# S7CAS-PLEIADES-CARTE-MERE_Pxx_PHY.net
KiCad netlist of a schematic drawn in Altium Designer
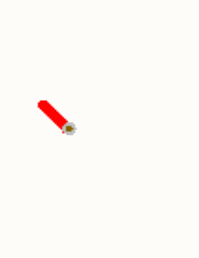
[diagram p0: S7CAS-PLEIADES-CARTE-MERE_Pxx_PHY.SchDoc, left]
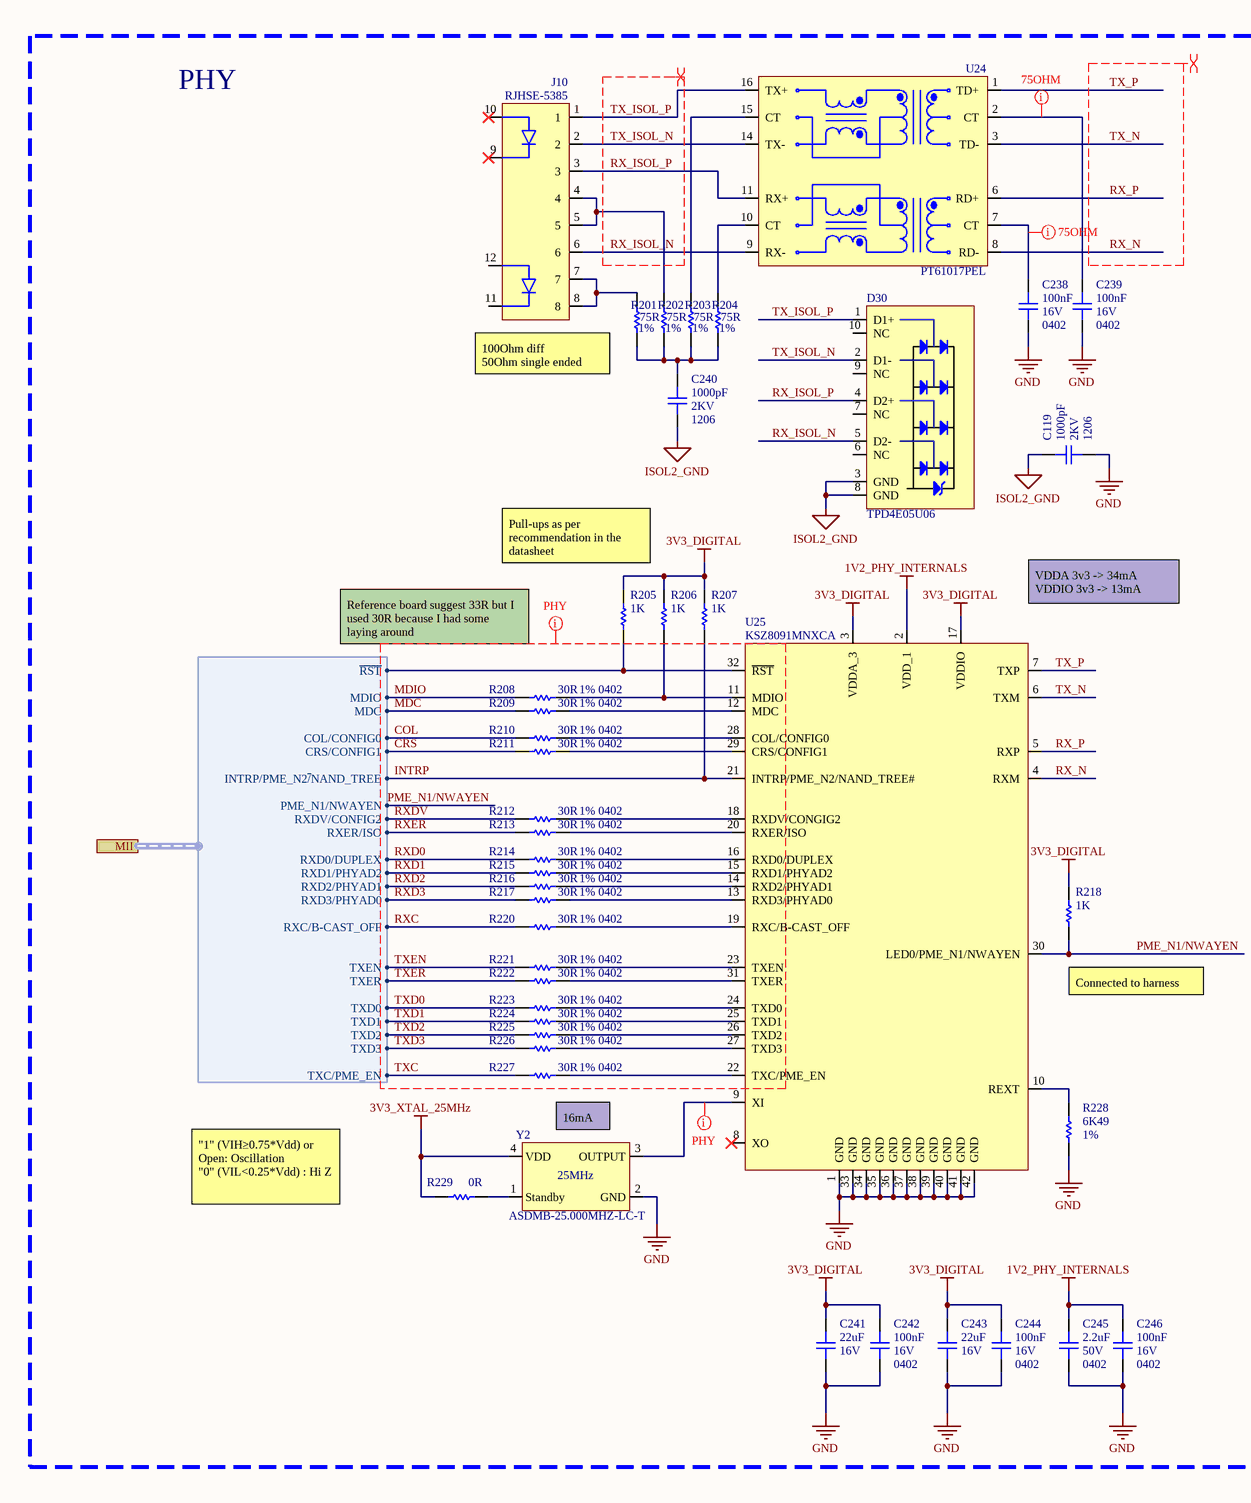
[diagram p1: S7CAS-PLEIADES-CARTE-MERE_Pxx_PHY.SchDoc, middle]
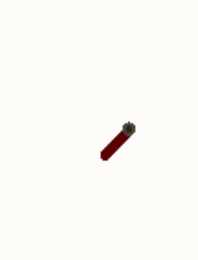
[diagram p2: S7CAS-PLEIADES-CARTE-MERE_Pxx_PHY.SchDoc, right]

(export (version "E")
  (design (tool "Eeschema 10.0.6"))
  (components
    (comp (ref "C119")
      (value "1000pF")
      (footprint "S7CAS_LIB2023:CAP_1206")
      (description "CAP - 1206")
      (fields
        (field (name "VOLTAGE") "2KV")
        (field (name "PACKAGE") "1206")
        (field (name "CREATEDBY") "Jonathan Bouchard")
      )
      (libsource (lib "S7CAS_LIB2023") (part "CAP - 1206"))
    )
    (comp (ref "C238")
      (value "100nF")
      (footprint "S7CAS_LIB2023:CAP_0402")
      (description "CAP - 0402")
      (fields
        (field (name "VOLTAGE") "16V")
        (field (name "PACKAGE") "0402")
        (field (name "Comment") "0402")
        (field (name "CREATEDBY") "Jonathan Bouchard")
      )
      (libsource (lib "S7CAS_LIB2023") (part "CAP - 0603"))
    )
    (comp (ref "C239")
      (value "100nF")
      (footprint "S7CAS_LIB2023:CAP_0402")
      (description "CAP - 0402")
      (fields
        (field (name "VOLTAGE") "16V")
        (field (name "PACKAGE") "0402")
        (field (name "Comment") "0402")
        (field (name "CREATEDBY") "Jonathan Bouchard")
      )
      (libsource (lib "S7CAS_LIB2023") (part "CAP - 0603"))
    )
    (comp (ref "C240")
      (value "1000pF")
      (footprint "S7CAS_LIB2023:CAP_1206")
      (description "CAP - 1206")
      (fields
        (field (name "VOLTAGE") "2KV")
        (field (name "PACKAGE") "1206")
        (field (name "CREATEDBY") "Jonathan Bouchard")
      )
      (libsource (lib "S7CAS_LIB2023") (part "CAP - 1206"))
    )
    (comp (ref "C241")
      (value "22uF")
      (footprint "S7CAS_LIB2023:CAP_1206")
      (description "CAP - 1206")
      (fields (field (name "VOLTAGE") "16V") (field (name "CREATEDBY") "Jonathan Bouchard"))
      (libsource (lib "S7CAS_LIB2023") (part "CAP - 1206"))
    )
    (comp (ref "C242")
      (value "100nF")
      (footprint "S7CAS_LIB2023:CAP_0402")
      (description "CAP - 0402")
      (fields
        (field (name "VOLTAGE") "16V")
        (field (name "PACKAGE") "0402")
        (field (name "Comment") "0402")
        (field (name "CREATEDBY") "Jonathan Bouchard")
      )
      (libsource (lib "S7CAS_LIB2023") (part "CAP - 0603"))
    )
    (comp (ref "C243")
      (value "22uF")
      (footprint "S7CAS_LIB2023:CAP_1206")
      (description "CAP - 1206")
      (fields (field (name "VOLTAGE") "16V") (field (name "CREATEDBY") "Jonathan Bouchard"))
      (libsource (lib "S7CAS_LIB2023") (part "CAP - 1206"))
    )
    (comp (ref "C244")
      (value "100nF")
      (footprint "S7CAS_LIB2023:CAP_0402")
      (description "CAP - 0402")
      (fields
        (field (name "VOLTAGE") "16V")
        (field (name "PACKAGE") "0402")
        (field (name "Comment") "0402")
        (field (name "CREATEDBY") "Jonathan Bouchard")
      )
      (libsource (lib "S7CAS_LIB2023") (part "CAP - 0603"))
    )
    (comp (ref "C245")
      (value "2.2uF")
      (footprint "S7CAS_LIB2023:CAP_0402")
      (description "CAP - 0402")
      (fields
        (field (name "VOLTAGE") "50V")
        (field (name "PACKAGE") "0402")
        (field (name "Comment") "0402")
        (field (name "CREATEDBY") "Jonathan Bouchard")
      )
      (libsource (lib "S7CAS_LIB2023") (part "CAP - 0603"))
    )
    (comp (ref "C246")
      (value "100nF")
      (footprint "S7CAS_LIB2023:CAP_0402")
      (description "CAP - 0402")
      (fields
        (field (name "VOLTAGE") "16V")
        (field (name "PACKAGE") "0402")
        (field (name "Comment") "0402")
        (field (name "CREATEDBY") "Jonathan Bouchard")
      )
      (libsource (lib "S7CAS_LIB2023") (part "CAP - 0603"))
    )
    (comp (ref "D30")
      (value "TPD4E05U06")
      (footprint "TVS_DATA_TPD4E05U06")
      (description "TVS - TVS DIODE 5.5VWM 14VC - 10SON")
      (fields
        (field (name "CREATEDBY/DATE") "Olivier Bernard / 12/3/2018")
        (field (name "VERIFIEDBY") "Caroline Paulin / 4 juillet 2018")
      )
      (libsource (lib "S7CAS_LIB2023") (part "TVS_DATA_TPD4E05U06"))
    )
    (comp (ref "J10")
      (value "RJHSE-5385")
      (footprint "CONN_ETHERNET_RJHSE-5385")
      (description "CONN - MOD JACK RJ45 R/A ETHERNET - TH")
      (fields (field (name "MFG") "Amphenol") (field (name "CREATEDBY") "Jonathan Bouchard"))
      (libsource (lib "S7CAS_LIB2023") (part "CONN_ETHERNET_RJHSE-5385"))
    )
    (comp (ref "R201")
      (value "75R")
      (footprint "S7CAS_LIB2023:RES_0402")
      (description "RES - 0402")
      (fields
        (field (name "PRECISION") "1%")
        (field (name "Comment") "RES - 0603")
        (field (name "CREATEDBY") "Jonathan Bouchard")
      )
      (libsource (lib "S7CAS_LIB2023") (part "RES - 0603"))
    )
    (comp (ref "R202")
      (value "75R")
      (footprint "S7CAS_LIB2023:RES_0402")
      (description "RES - 0402")
      (fields
        (field (name "PRECISION") "1%")
        (field (name "Comment") "RES - 0603")
        (field (name "CREATEDBY") "Jonathan Bouchard")
      )
      (libsource (lib "S7CAS_LIB2023") (part "RES - 0603"))
    )
    (comp (ref "R203")
      (value "75R")
      (footprint "S7CAS_LIB2023:RES_0402")
      (description "RES - 0402")
      (fields
        (field (name "PRECISION") "1%")
        (field (name "Comment") "RES - 0603")
        (field (name "CREATEDBY") "Jonathan Bouchard")
      )
      (libsource (lib "S7CAS_LIB2023") (part "RES - 0603"))
    )
    (comp (ref "R204")
      (value "75R")
      (footprint "S7CAS_LIB2023:RES_0402")
      (description "RES - 0402")
      (fields
        (field (name "PRECISION") "1%")
        (field (name "Comment") "RES - 0603")
        (field (name "CREATEDBY") "Jonathan Bouchard")
      )
      (libsource (lib "S7CAS_LIB2023") (part "RES - 0603"))
    )
    (comp (ref "R205")
      (value "1K")
      (footprint "S7CAS_LIB2023:RES_0402")
      (description "RES - 0402")
      (fields (field (name "Comment") "RES - 0603") (field (name "CREATEDBY") "Jonathan Bouchard"))
      (libsource (lib "S7CAS_LIB2023") (part "RES - 0603"))
    )
    (comp (ref "R206")
      (value "1K")
      (footprint "S7CAS_LIB2023:RES_0402")
      (description "RES - 0402")
      (fields (field (name "Comment") "RES - 0603") (field (name "CREATEDBY") "Jonathan Bouchard"))
      (libsource (lib "S7CAS_LIB2023") (part "RES - 0603"))
    )
    (comp (ref "R207")
      (value "1K")
      (footprint "S7CAS_LIB2023:RES_0402")
      (description "RES - 0402")
      (fields (field (name "Comment") "RES - 0603") (field (name "CREATEDBY") "Jonathan Bouchard"))
      (libsource (lib "S7CAS_LIB2023") (part "RES - 0603"))
    )
    (comp (ref "R208")
      (value "30R")
      (footprint "S7CAS_LIB2023:RES_0402")
      (description "RES - 0402")
      (fields
        (field (name "PACKAGE") "0402")
        (field (name "PRECISION") "1%")
        (field (name "Comment") "RES - 0603")
        (field (name "CREATEDBY") "Jonathan Bouchard")
      )
      (libsource (lib "S7CAS_LIB2023") (part "RES - 0603"))
    )
    (comp (ref "R209")
      (value "30R")
      (footprint "S7CAS_LIB2023:RES_0402")
      (description "RES - 0402")
      (fields
        (field (name "PACKAGE") "0402")
        (field (name "PRECISION") "1%")
        (field (name "Comment") "RES - 0603")
        (field (name "CREATEDBY") "Jonathan Bouchard")
      )
      (libsource (lib "S7CAS_LIB2023") (part "RES - 0603"))
    )
    (comp (ref "R210")
      (value "30R")
      (footprint "S7CAS_LIB2023:RES_0402")
      (description "RES - 0402")
      (fields
        (field (name "PACKAGE") "0402")
        (field (name "PRECISION") "1%")
        (field (name "Comment") "RES - 0603")
        (field (name "CREATEDBY") "Jonathan Bouchard")
      )
      (libsource (lib "S7CAS_LIB2023") (part "RES - 0603"))
    )
    (comp (ref "R211")
      (value "30R")
      (footprint "S7CAS_LIB2023:RES_0402")
      (description "RES - 0402")
      (fields
        (field (name "PACKAGE") "0402")
        (field (name "PRECISION") "1%")
        (field (name "Comment") "RES - 0603")
        (field (name "CREATEDBY") "Jonathan Bouchard")
      )
      (libsource (lib "S7CAS_LIB2023") (part "RES - 0603"))
    )
    (comp (ref "R212")
      (value "30R")
      (footprint "S7CAS_LIB2023:RES_0402")
      (description "RES - 0402")
      (fields
        (field (name "PACKAGE") "0402")
        (field (name "PRECISION") "1%")
        (field (name "Comment") "RES - 0603")
        (field (name "CREATEDBY") "Jonathan Bouchard")
      )
      (libsource (lib "S7CAS_LIB2023") (part "RES - 0603"))
    )
    (comp (ref "R213")
      (value "30R")
      (footprint "S7CAS_LIB2023:RES_0402")
      (description "RES - 0402")
      (fields
        (field (name "PACKAGE") "0402")
        (field (name "PRECISION") "1%")
        (field (name "Comment") "RES - 0603")
        (field (name "CREATEDBY") "Jonathan Bouchard")
      )
      (libsource (lib "S7CAS_LIB2023") (part "RES - 0603"))
    )
    (comp (ref "R214")
      (value "30R")
      (footprint "S7CAS_LIB2023:RES_0402")
      (description "RES - 0402")
      (fields
        (field (name "PACKAGE") "0402")
        (field (name "PRECISION") "1%")
        (field (name "Comment") "RES - 0603")
        (field (name "CREATEDBY") "Jonathan Bouchard")
      )
      (libsource (lib "S7CAS_LIB2023") (part "RES - 0603"))
    )
    (comp (ref "R215")
      (value "30R")
      (footprint "S7CAS_LIB2023:RES_0402")
      (description "RES - 0402")
      (fields
        (field (name "PACKAGE") "0402")
        (field (name "PRECISION") "1%")
        (field (name "Comment") "RES - 0603")
        (field (name "CREATEDBY") "Jonathan Bouchard")
      )
      (libsource (lib "S7CAS_LIB2023") (part "RES - 0603"))
    )
    (comp (ref "R216")
      (value "30R")
      (footprint "S7CAS_LIB2023:RES_0402")
      (description "RES - 0402")
      (fields
        (field (name "PACKAGE") "0402")
        (field (name "PRECISION") "1%")
        (field (name "Comment") "RES - 0603")
        (field (name "CREATEDBY") "Jonathan Bouchard")
      )
      (libsource (lib "S7CAS_LIB2023") (part "RES - 0603"))
    )
    (comp (ref "R217")
      (value "30R")
      (footprint "S7CAS_LIB2023:RES_0402")
      (description "RES - 0402")
      (fields
        (field (name "PACKAGE") "0402")
        (field (name "PRECISION") "1%")
        (field (name "Comment") "RES - 0603")
        (field (name "CREATEDBY") "Jonathan Bouchard")
      )
      (libsource (lib "S7CAS_LIB2023") (part "RES - 0603"))
    )
    (comp (ref "R218")
      (value "1K")
      (footprint "S7CAS_LIB2023:RES_0402")
      (description "RES - 0402")
      (fields (field (name "Comment") "RES - 0603") (field (name "CREATEDBY") "Jonathan Bouchard"))
      (libsource (lib "S7CAS_LIB2023") (part "RES - 0603"))
    )
    (comp (ref "R220")
      (value "30R")
      (footprint "S7CAS_LIB2023:RES_0402")
      (description "RES - 0402")
      (fields
        (field (name "PACKAGE") "0402")
        (field (name "PRECISION") "1%")
        (field (name "Comment") "RES - 0603")
        (field (name "CREATEDBY") "Jonathan Bouchard")
      )
      (libsource (lib "S7CAS_LIB2023") (part "RES - 0603"))
    )
    (comp (ref "R221")
      (value "30R")
      (footprint "S7CAS_LIB2023:RES_0402")
      (description "RES - 0402")
      (fields
        (field (name "PACKAGE") "0402")
        (field (name "PRECISION") "1%")
        (field (name "Comment") "RES - 0603")
        (field (name "CREATEDBY") "Jonathan Bouchard")
      )
      (libsource (lib "S7CAS_LIB2023") (part "RES - 0603"))
    )
    (comp (ref "R222")
      (value "30R")
      (footprint "S7CAS_LIB2023:RES_0402")
      (description "RES - 0402")
      (fields
        (field (name "PACKAGE") "0402")
        (field (name "PRECISION") "1%")
        (field (name "Comment") "RES - 0603")
        (field (name "CREATEDBY") "Jonathan Bouchard")
      )
      (libsource (lib "S7CAS_LIB2023") (part "RES - 0603"))
    )
    (comp (ref "R223")
      (value "30R")
      (footprint "S7CAS_LIB2023:RES_0402")
      (description "RES - 0402")
      (fields
        (field (name "PACKAGE") "0402")
        (field (name "PRECISION") "1%")
        (field (name "Comment") "RES - 0603")
        (field (name "CREATEDBY") "Jonathan Bouchard")
      )
      (libsource (lib "S7CAS_LIB2023") (part "RES - 0603"))
    )
    (comp (ref "R224")
      (value "30R")
      (footprint "S7CAS_LIB2023:RES_0402")
      (description "RES - 0402")
      (fields
        (field (name "PACKAGE") "0402")
        (field (name "PRECISION") "1%")
        (field (name "Comment") "RES - 0603")
        (field (name "CREATEDBY") "Jonathan Bouchard")
      )
      (libsource (lib "S7CAS_LIB2023") (part "RES - 0603"))
    )
    (comp (ref "R225")
      (value "30R")
      (footprint "S7CAS_LIB2023:RES_0402")
      (description "RES - 0402")
      (fields
        (field (name "PACKAGE") "0402")
        (field (name "PRECISION") "1%")
        (field (name "Comment") "RES - 0603")
        (field (name "CREATEDBY") "Jonathan Bouchard")
      )
      (libsource (lib "S7CAS_LIB2023") (part "RES - 0603"))
    )
    (comp (ref "R226")
      (value "30R")
      (footprint "S7CAS_LIB2023:RES_0402")
      (description "RES - 0402")
      (fields
        (field (name "PACKAGE") "0402")
        (field (name "PRECISION") "1%")
        (field (name "Comment") "RES - 0603")
        (field (name "CREATEDBY") "Jonathan Bouchard")
      )
      (libsource (lib "S7CAS_LIB2023") (part "RES - 0603"))
    )
    (comp (ref "R227")
      (value "30R")
      (footprint "S7CAS_LIB2023:RES_0402")
      (description "RES - 0402")
      (fields
        (field (name "PACKAGE") "0402")
        (field (name "PRECISION") "1%")
        (field (name "Comment") "RES - 0603")
        (field (name "CREATEDBY") "Jonathan Bouchard")
      )
      (libsource (lib "S7CAS_LIB2023") (part "RES - 0603"))
    )
    (comp (ref "R228")
      (value "6K49")
      (footprint "RES_0402")
      (description "RES - 0402")
      (fields
        (field (name "VOLTAGE") "50V")
        (field (name "POWER") "1/16W")
        (field (name "PRECISION") "1%")
        (field (name "CREATEDBY") "Jonathan Bouchard")
      )
      (libsource (lib "S7CAS_LIB2023") (part "RES - 0402"))
    )
    (comp (ref "R229")
      (value "0R")
      (footprint "S7CAS_LIB2023:RES_0402")
      (description "RES - 0402")
      (fields (field (name "Comment") "RES - 0603") (field (name "CREATEDBY") "Jonathan Bouchard"))
      (libsource (lib "S7CAS_LIB2023") (part "RES - 0603"))
    )
    (comp (ref "U24")
      (value "PT61017PEL")
      (footprint "ISO_PT61017PEL")
      (description "ISO - 350µH LAN 10/100 Base-T Pulse Transformer 1CT:1CT Surface Mount")
      (libsource (lib "S7CAS_LIB2023") (part "ISO_PT61017PEL"))
    )
    (comp (ref "U25")
      (value "KSZ8091MNXCA")
      (footprint "COM_ETH_PHY_KSZ8091MNXCA")
      (description "COM - ETHERNET PHY 10/100 - QFN-32")
      (fields
        (field (name "VOLTAGE") "1.8V, 2.5V, 3.3V")
        (field (name "MFG") "Micrel")
        (field (name "CREATEDBY") "Jonathan Bouchard")
      )
      (libsource (lib "S7CAS_LIB2023") (part "COM_ETH_PHY_KSZ8091MNXCA"))
    )
    (comp (ref "Y2")
      (value "ASDMB-25.000MHZ-LC-T")
      (footprint "OSC_ASDMB-25.000MHZ-LC-T")
      (description "OSC - 25MHz XO (Standard) LVCMOS - 4-SMD, No Lead")
      (fields
        (field (name "TOLERANCE") "±50ppm")
        (field (name "CREATEDBY/DATE") "Joël Lemay 2019-03-29")
        (field (name "VERIFIEDBY") "C. Paulin - 29 mai 2019")
      )
      (libsource (lib "S7CAS_LIB2023") (part "OSC_ASDMB-25.000MHZ-LC-T"))
    )
  )
  (nets
    (net (code "4") (name "/COL") (class "Default")
      (node (ref "R210") (pin "1") (pinfunction "1_1") (pintype "passive"))
    )
    (net (code "5") (name "/CRS") (class "Default")
      (node (ref "R211") (pin "1") (pinfunction "1_1") (pintype "passive"))
    )
    (net (code "6") (name "/INTRP") (class "Default")
      (node (ref "R207") (pin "1") (pinfunction "1_1") (pintype "passive"))
      (node (ref "U25") (pin "21") (pinfunction "INTRP/PME_N2/NAND_TREE#_21") (pintype "passive"))
    )
    (net (code "7") (name "/MDC") (class "Default")
      (node (ref "R209") (pin "1") (pinfunction "1_1") (pintype "passive"))
    )
    (net (code "8") (name "/MDIO") (class "Default")
      (node (ref "R208") (pin "1") (pinfunction "1_1") (pintype "passive"))
    )
    (net (code "9") (name "/PME_N1{slash}NWAYEN") (class "Default")
      (node (ref "R218") (pin "1") (pinfunction "1_1") (pintype "passive"))
      (node (ref "U25") (pin "30") (pinfunction "LED0/PME_N1/NWAYEN_30") (pintype "passive"))
    )
    (net (code "10") (name "/RXC") (class "Default")
      (node (ref "R220") (pin "1") (pinfunction "1_1") (pintype "passive"))
    )
    (net (code "11") (name "/RXD0") (class "Default")
      (node (ref "R214") (pin "1") (pinfunction "1_1") (pintype "passive"))
    )
    (net (code "12") (name "/RXD1") (class "Default")
      (node (ref "R215") (pin "1") (pinfunction "1_1") (pintype "passive"))
    )
    (net (code "13") (name "/RXD2") (class "Default")
      (node (ref "R216") (pin "1") (pinfunction "1_1") (pintype "passive"))
    )
    (net (code "14") (name "/RXD3") (class "Default")
      (node (ref "R217") (pin "1") (pinfunction "1_1") (pintype "passive"))
    )
    (net (code "15") (name "/RXDV") (class "Default")
      (node (ref "R212") (pin "1") (pinfunction "1_1") (pintype "passive"))
    )
    (net (code "16") (name "/RXER") (class "Default")
      (node (ref "R213") (pin "1") (pinfunction "1_1") (pintype "passive"))
    )
    (net (code "17") (name "/RX_ISOL_N") (class "Default")
      (node (ref "D30") (pin "5") (pinfunction "D2-_5") (pintype "passive"))
      (node (ref "J10") (pin "6") (pinfunction "6_6") (pintype "passive"))
      (node (ref "U24") (pin "9") (pinfunction "RX-_9") (pintype "passive"))
    )
    (net (code "18") (name "/RX_ISOL_P") (class "Default")
      (node (ref "D30") (pin "4") (pinfunction "D2+_4") (pintype "passive"))
      (node (ref "J10") (pin "3") (pinfunction "3_3") (pintype "passive"))
      (node (ref "U24") (pin "11") (pinfunction "RX+_11") (pintype "passive"))
    )
    (net (code "19") (name "/RX_N") (class "Default")
      (node (ref "U24") (pin "8") (pinfunction "RD-_8") (pintype "passive"))
      (node (ref "U25") (pin "4") (pinfunction "RXM_4") (pintype "passive"))
    )
    (net (code "20") (name "/RX_P") (class "Default")
      (node (ref "U24") (pin "6") (pinfunction "RD+_6") (pintype "passive"))
      (node (ref "U25") (pin "5") (pinfunction "RXP_5") (pintype "passive"))
    )
    (net (code "21") (name "/TXC") (class "Default")
      (node (ref "R227") (pin "1") (pinfunction "1_1") (pintype "passive"))
    )
    (net (code "22") (name "/TXD0") (class "Default")
      (node (ref "R223") (pin "1") (pinfunction "1_1") (pintype "passive"))
    )
    (net (code "23") (name "/TXD1") (class "Default")
      (node (ref "R224") (pin "1") (pinfunction "1_1") (pintype "passive"))
    )
    (net (code "24") (name "/TXD2") (class "Default")
      (node (ref "R225") (pin "1") (pinfunction "1_1") (pintype "passive"))
    )
    (net (code "25") (name "/TXD3") (class "Default")
      (node (ref "R226") (pin "1") (pinfunction "1_1") (pintype "passive"))
    )
    (net (code "26") (name "/TXEN") (class "Default")
      (node (ref "R221") (pin "1") (pinfunction "1_1") (pintype "passive"))
    )
    (net (code "27") (name "/TXER") (class "Default")
      (node (ref "R222") (pin "1") (pinfunction "1_1") (pintype "passive"))
    )
    (net (code "28") (name "/TX_ISOL_N") (class "Default")
      (node (ref "D30") (pin "2") (pinfunction "D1-_2") (pintype "passive"))
      (node (ref "J10") (pin "2") (pinfunction "2_2") (pintype "passive"))
      (node (ref "U24") (pin "14") (pinfunction "TX-_14") (pintype "passive"))
    )
    (net (code "29") (name "/TX_ISOL_P") (class "Default")
      (node (ref "D30") (pin "1") (pinfunction "D1+_1") (pintype "passive"))
      (node (ref "J10") (pin "1") (pinfunction "1_1") (pintype "passive"))
      (node (ref "U24") (pin "16") (pinfunction "TX+_16") (pintype "passive"))
    )
    (net (code "30") (name "/TX_N") (class "Default")
      (node (ref "U24") (pin "3") (pinfunction "TD-_3") (pintype "passive"))
      (node (ref "U25") (pin "6") (pinfunction "TXM_6") (pintype "passive"))
    )
    (net (code "31") (name "/TX_P") (class "Default")
      (node (ref "U24") (pin "1") (pinfunction "TD+_1") (pintype "passive"))
      (node (ref "U25") (pin "7") (pinfunction "TXP_7") (pintype "passive"))
    )
    (net (code "33") (name "1V2_PHY_INTERNALS") (class "Default")
      (node (ref "C245") (pin "2") (pinfunction "2_2") (pintype "passive"))
      (node (ref "C246") (pin "2") (pinfunction "2_2") (pintype "passive"))
      (node (ref "U25") (pin "2") (pinfunction "VDD_1_2") (pintype "power_in"))
    )
    (net (code "34") (name "3V3_DIGITAL") (class "Default")
      (node (ref "C241") (pin "2") (pinfunction "2_2") (pintype "passive"))
      (node (ref "C242") (pin "2") (pinfunction "2_2") (pintype "passive"))
      (node (ref "C243") (pin "2") (pinfunction "2_2") (pintype "passive"))
      (node (ref "C244") (pin "2") (pinfunction "2_2") (pintype "passive"))
      (node (ref "R205") (pin "2") (pinfunction "2_2") (pintype "passive"))
      (node (ref "R206") (pin "2") (pinfunction "2_2") (pintype "passive"))
      (node (ref "R207") (pin "2") (pinfunction "2_2") (pintype "passive"))
      (node (ref "R218") (pin "2") (pinfunction "2_2") (pintype "passive"))
      (node (ref "U25") (pin "17") (pinfunction "VDDIO_17") (pintype "power_in"))
      (node (ref "U25") (pin "3") (pinfunction "VDDA_3_3") (pintype "power_in"))
    )
    (net (code "35") (name "3V3_XTAL_25MHz") (class "Default")
      (node (ref "R229") (pin "2") (pinfunction "2_2") (pintype "passive"))
      (node (ref "Y2") (pin "4") (pinfunction "VDD_4") (pintype "passive"))
    )
    (net (code "36") (name "GND") (class "Default")
      (node (ref "C119") (pin "1") (pinfunction "1_1") (pintype "passive"))
      (node (ref "C238") (pin "1") (pinfunction "1_1") (pintype "passive"))
      (node (ref "C239") (pin "1") (pinfunction "1_1") (pintype "passive"))
      (node (ref "C241") (pin "1") (pinfunction "1_1") (pintype "passive"))
      (node (ref "C242") (pin "1") (pinfunction "1_1") (pintype "passive"))
      (node (ref "C243") (pin "1") (pinfunction "1_1") (pintype "passive"))
      (node (ref "C244") (pin "1") (pinfunction "1_1") (pintype "passive"))
      (node (ref "C245") (pin "1") (pinfunction "1_1") (pintype "passive"))
      (node (ref "C246") (pin "1") (pinfunction "1_1") (pintype "passive"))
      (node (ref "R228") (pin "1") (pinfunction "1_1") (pintype "passive"))
      (node (ref "U25") (pin "1") (pinfunction "GND_1") (pintype "passive"))
      (node (ref "U25") (pin "33") (pinfunction "GND_33") (pintype "passive"))
      (node (ref "U25") (pin "34") (pinfunction "GND_34") (pintype "passive"))
      (node (ref "U25") (pin "35") (pinfunction "GND_35") (pintype "passive"))
      (node (ref "U25") (pin "36") (pinfunction "GND_36") (pintype "passive"))
      (node (ref "U25") (pin "37") (pinfunction "GND_37") (pintype "passive"))
      (node (ref "U25") (pin "38") (pinfunction "GND_38") (pintype "passive"))
      (node (ref "U25") (pin "39") (pinfunction "GND_39") (pintype "passive"))
      (node (ref "U25") (pin "40") (pinfunction "GND_40") (pintype "passive"))
      (node (ref "U25") (pin "41") (pinfunction "GND_41") (pintype "passive"))
      (node (ref "U25") (pin "42") (pinfunction "GND_42") (pintype "passive"))
      (node (ref "Y2") (pin "2") (pinfunction "GND_2") (pintype "passive"))
    )
    (net (code "37") (name "ISOL2_GND") (class "Default")
      (node (ref "C119") (pin "2") (pinfunction "2_2") (pintype "passive"))
      (node (ref "C240") (pin "1") (pinfunction "1_1") (pintype "passive"))
      (node (ref "D30") (pin "3") (pinfunction "GND_3") (pintype "passive"))
      (node (ref "D30") (pin "8") (pinfunction "GND_8") (pintype "passive"))
    )
    (net (code "38") (name "Net-(C238-Pad2)") (class "Default")
      (node (ref "C238") (pin "2") (pinfunction "2_2") (pintype "passive"))
      (node (ref "U24") (pin "7") (pinfunction "CT_7") (pintype "passive"))
    )
    (net (code "39") (name "Net-(C239-Pad2)") (class "Default")
      (node (ref "C239") (pin "2") (pinfunction "2_2") (pintype "passive"))
      (node (ref "U24") (pin "2") (pinfunction "CT_2") (pintype "passive"))
    )
    (net (code "40") (name "Net-(C240-Pad2)") (class "Default")
      (node (ref "C240") (pin "2") (pinfunction "2_2") (pintype "passive"))
      (node (ref "R201") (pin "1") (pinfunction "1_1") (pintype "passive"))
      (node (ref "R202") (pin "1") (pinfunction "1_1") (pintype "passive"))
      (node (ref "R203") (pin "1") (pinfunction "1_1") (pintype "passive"))
      (node (ref "R204") (pin "1") (pinfunction "1_1") (pintype "passive"))
    )
    (net (code "41") (name "Net-(J10-Pad4)") (class "Default")
      (node (ref "J10") (pin "4") (pinfunction "4_4") (pintype "passive"))
      (node (ref "J10") (pin "5") (pinfunction "5_5") (pintype "passive"))
      (node (ref "R202") (pin "2") (pinfunction "2_2") (pintype "passive"))
    )
    (net (code "42") (name "Net-(J10-Pad7)") (class "Default")
      (node (ref "J10") (pin "7") (pinfunction "7_7") (pintype "passive"))
      (node (ref "J10") (pin "8") (pinfunction "8_8") (pintype "passive"))
      (node (ref "R201") (pin "2") (pinfunction "2_2") (pintype "passive"))
    )
    (net (code "43") (name "Net-(R203-Pad2)") (class "Default")
      (node (ref "R203") (pin "2") (pinfunction "2_2") (pintype "passive"))
      (node (ref "U24") (pin "15") (pinfunction "CT_15") (pintype "passive"))
    )
    (net (code "44") (name "Net-(R204-Pad2)") (class "Default")
      (node (ref "R204") (pin "2") (pinfunction "2_2") (pintype "passive"))
      (node (ref "U24") (pin "10") (pinfunction "CT_10") (pintype "passive"))
    )
    (net (code "45") (name "Net-(U25-COL{slash}CONFIG0)") (class "Default")
      (node (ref "R210") (pin "2") (pinfunction "2_2") (pintype "passive"))
      (node (ref "U25") (pin "28") (pinfunction "COL/CONFIG0_28") (pintype "passive"))
    )
    (net (code "46") (name "Net-(U25-CRS{slash}CONFIG1)") (class "Default")
      (node (ref "R211") (pin "2") (pinfunction "2_2") (pintype "passive"))
      (node (ref "U25") (pin "29") (pinfunction "CRS/CONFIG1_29") (pintype "passive"))
    )
    (net (code "47") (name "Net-(U25-MDC)") (class "Default")
      (node (ref "R209") (pin "2") (pinfunction "2_2") (pintype "passive"))
      (node (ref "U25") (pin "12") (pinfunction "MDC_12") (pintype "passive"))
    )
    (net (code "48") (name "Net-(U25-MDIO)") (class "Default")
      (node (ref "R206") (pin "1") (pinfunction "1_1") (pintype "passive"))
      (node (ref "R208") (pin "2") (pinfunction "2_2") (pintype "passive"))
      (node (ref "U25") (pin "11") (pinfunction "MDIO_11") (pintype "passive"))
    )
    (net (code "49") (name "Net-(U25-REXT)") (class "Default")
      (node (ref "R228") (pin "2") (pinfunction "2_2") (pintype "passive"))
      (node (ref "U25") (pin "10") (pinfunction "REXT_10") (pintype "passive"))
    )
    (net (code "50") (name "Net-(U25-RST)") (class "Default")
      (node (ref "R205") (pin "1") (pinfunction "1_1") (pintype "passive"))
      (node (ref "U25") (pin "32") (pinfunction "RST_32") (pintype "passive"))
    )
    (net (code "51") (name "Net-(U25-RXC{slash}B-CAST_OFF)") (class "Default")
      (node (ref "R220") (pin "2") (pinfunction "2_2") (pintype "passive"))
      (node (ref "U25") (pin "19") (pinfunction "RXC/B-CAST_OFF_19") (pintype "passive"))
    )
    (net (code "52") (name "Net-(U25-RXD0{slash}DUPLEX)") (class "Default")
      (node (ref "R214") (pin "2") (pinfunction "2_2") (pintype "passive"))
      (node (ref "U25") (pin "16") (pinfunction "RXD0/DUPLEX_16") (pintype "passive"))
    )
    (net (code "53") (name "Net-(U25-RXD1{slash}PHYAD2)") (class "Default")
      (node (ref "R215") (pin "2") (pinfunction "2_2") (pintype "passive"))
      (node (ref "U25") (pin "15") (pinfunction "RXD1/PHYAD2_15") (pintype "passive"))
    )
    (net (code "54") (name "Net-(U25-RXD2{slash}PHYAD1)") (class "Default")
      (node (ref "R216") (pin "2") (pinfunction "2_2") (pintype "passive"))
      (node (ref "U25") (pin "14") (pinfunction "RXD2/PHYAD1_14") (pintype "passive"))
    )
    (net (code "55") (name "Net-(U25-RXD3{slash}PHYAD0)") (class "Default")
      (node (ref "R217") (pin "2") (pinfunction "2_2") (pintype "passive"))
      (node (ref "U25") (pin "13") (pinfunction "RXD3/PHYAD0_13") (pintype "passive"))
    )
    (net (code "56") (name "Net-(U25-RXDV{slash}CONGIG2)") (class "Default")
      (node (ref "R212") (pin "2") (pinfunction "2_2") (pintype "passive"))
      (node (ref "U25") (pin "18") (pinfunction "RXDV/CONGIG2_18") (pintype "passive"))
    )
    (net (code "57") (name "Net-(U25-RXER{slash}ISO)") (class "Default")
      (node (ref "R213") (pin "2") (pinfunction "2_2") (pintype "passive"))
      (node (ref "U25") (pin "20") (pinfunction "RXER/ISO_20") (pintype "passive"))
    )
    (net (code "58") (name "Net-(U25-TXC{slash}PME_EN)") (class "Default")
      (node (ref "R227") (pin "2") (pinfunction "2_2") (pintype "passive"))
      (node (ref "U25") (pin "22") (pinfunction "TXC/PME_EN_22") (pintype "passive"))
    )
    (net (code "59") (name "Net-(U25-TXD0)") (class "Default")
      (node (ref "R223") (pin "2") (pinfunction "2_2") (pintype "passive"))
      (node (ref "U25") (pin "24") (pinfunction "TXD0_24") (pintype "passive"))
    )
    (net (code "60") (name "Net-(U25-TXD1)") (class "Default")
      (node (ref "R224") (pin "2") (pinfunction "2_2") (pintype "passive"))
      (node (ref "U25") (pin "25") (pinfunction "TXD1_25") (pintype "passive"))
    )
    (net (code "61") (name "Net-(U25-TXD2)") (class "Default")
      (node (ref "R225") (pin "2") (pinfunction "2_2") (pintype "passive"))
      (node (ref "U25") (pin "26") (pinfunction "TXD2_26") (pintype "passive"))
    )
    (net (code "62") (name "Net-(U25-TXD3)") (class "Default")
      (node (ref "R226") (pin "2") (pinfunction "2_2") (pintype "passive"))
      (node (ref "U25") (pin "27") (pinfunction "TXD3_27") (pintype "passive"))
    )
    (net (code "63") (name "Net-(U25-TXEN)") (class "Default")
      (node (ref "R221") (pin "2") (pinfunction "2_2") (pintype "passive"))
      (node (ref "U25") (pin "23") (pinfunction "TXEN_23") (pintype "passive"))
    )
    (net (code "64") (name "Net-(U25-TXER)") (class "Default")
      (node (ref "R222") (pin "2") (pinfunction "2_2") (pintype "passive"))
      (node (ref "U25") (pin "31") (pinfunction "TXER_31") (pintype "passive"))
    )
    (net (code "65") (name "Net-(U25-XI)") (class "Default")
      (node (ref "U25") (pin "9") (pinfunction "XI_9") (pintype "passive"))
      (node (ref "Y2") (pin "3") (pinfunction "OUTPUT_3") (pintype "passive"))
    )
    (net (code "66") (name "Net-(Y2-Standby)") (class "Default")
      (node (ref "R229") (pin "1") (pinfunction "1_1") (pintype "passive"))
      (node (ref "Y2") (pin "1") (pinfunction "Standby_1") (pintype "passive"))
    )
    (net (code "67") (name "unconnected-(D30-NC-Pad6)") (class "Default")
      (node (ref "D30") (pin "6") (pinfunction "NC_6") (pintype "passive"))
    )
    (net (code "68") (name "unconnected-(D30-NC-Pad7)") (class "Default")
      (node (ref "D30") (pin "7") (pinfunction "NC_7") (pintype "passive"))
    )
    (net (code "69") (name "unconnected-(D30-NC-Pad9)") (class "Default")
      (node (ref "D30") (pin "9") (pinfunction "NC_9") (pintype "passive"))
    )
    (net (code "70") (name "unconnected-(D30-NC-Pad10)") (class "Default")
      (node (ref "D30") (pin "10") (pinfunction "NC_10") (pintype "passive"))
    )
    (net (code "71") (name "unconnected-(J10-LED1_A-Pad10)") (class "Default")
      (node (ref "J10") (pin "10") (pinfunction "LED1_A_10") (pintype "passive+no_connect"))
    )
    (net (code "72") (name "unconnected-(J10-LED1_K-Pad9)") (class "Default")
      (node (ref "J10") (pin "9") (pinfunction "LED1_K_9") (pintype "passive+no_connect"))
    )
    (net (code "73") (name "unconnected-(J10-LED2_A-Pad12)") (class "Default")
      (node (ref "J10") (pin "12") (pinfunction "LED2_A_12") (pintype "passive"))
    )
    (net (code "74") (name "unconnected-(J10-LED2_K-Pad11)") (class "Default")
      (node (ref "J10") (pin "11") (pinfunction "LED2_K_11") (pintype "passive"))
    )
    (net (code "75") (name "unconnected-(U25-XO-Pad8)") (class "Default")
      (node (ref "U25") (pin "8") (pinfunction "XO_8") (pintype "passive+no_connect"))
    )
  )
)
